# 1A_driver.net
KiCad netlist of a schematic drawn in EAGLE
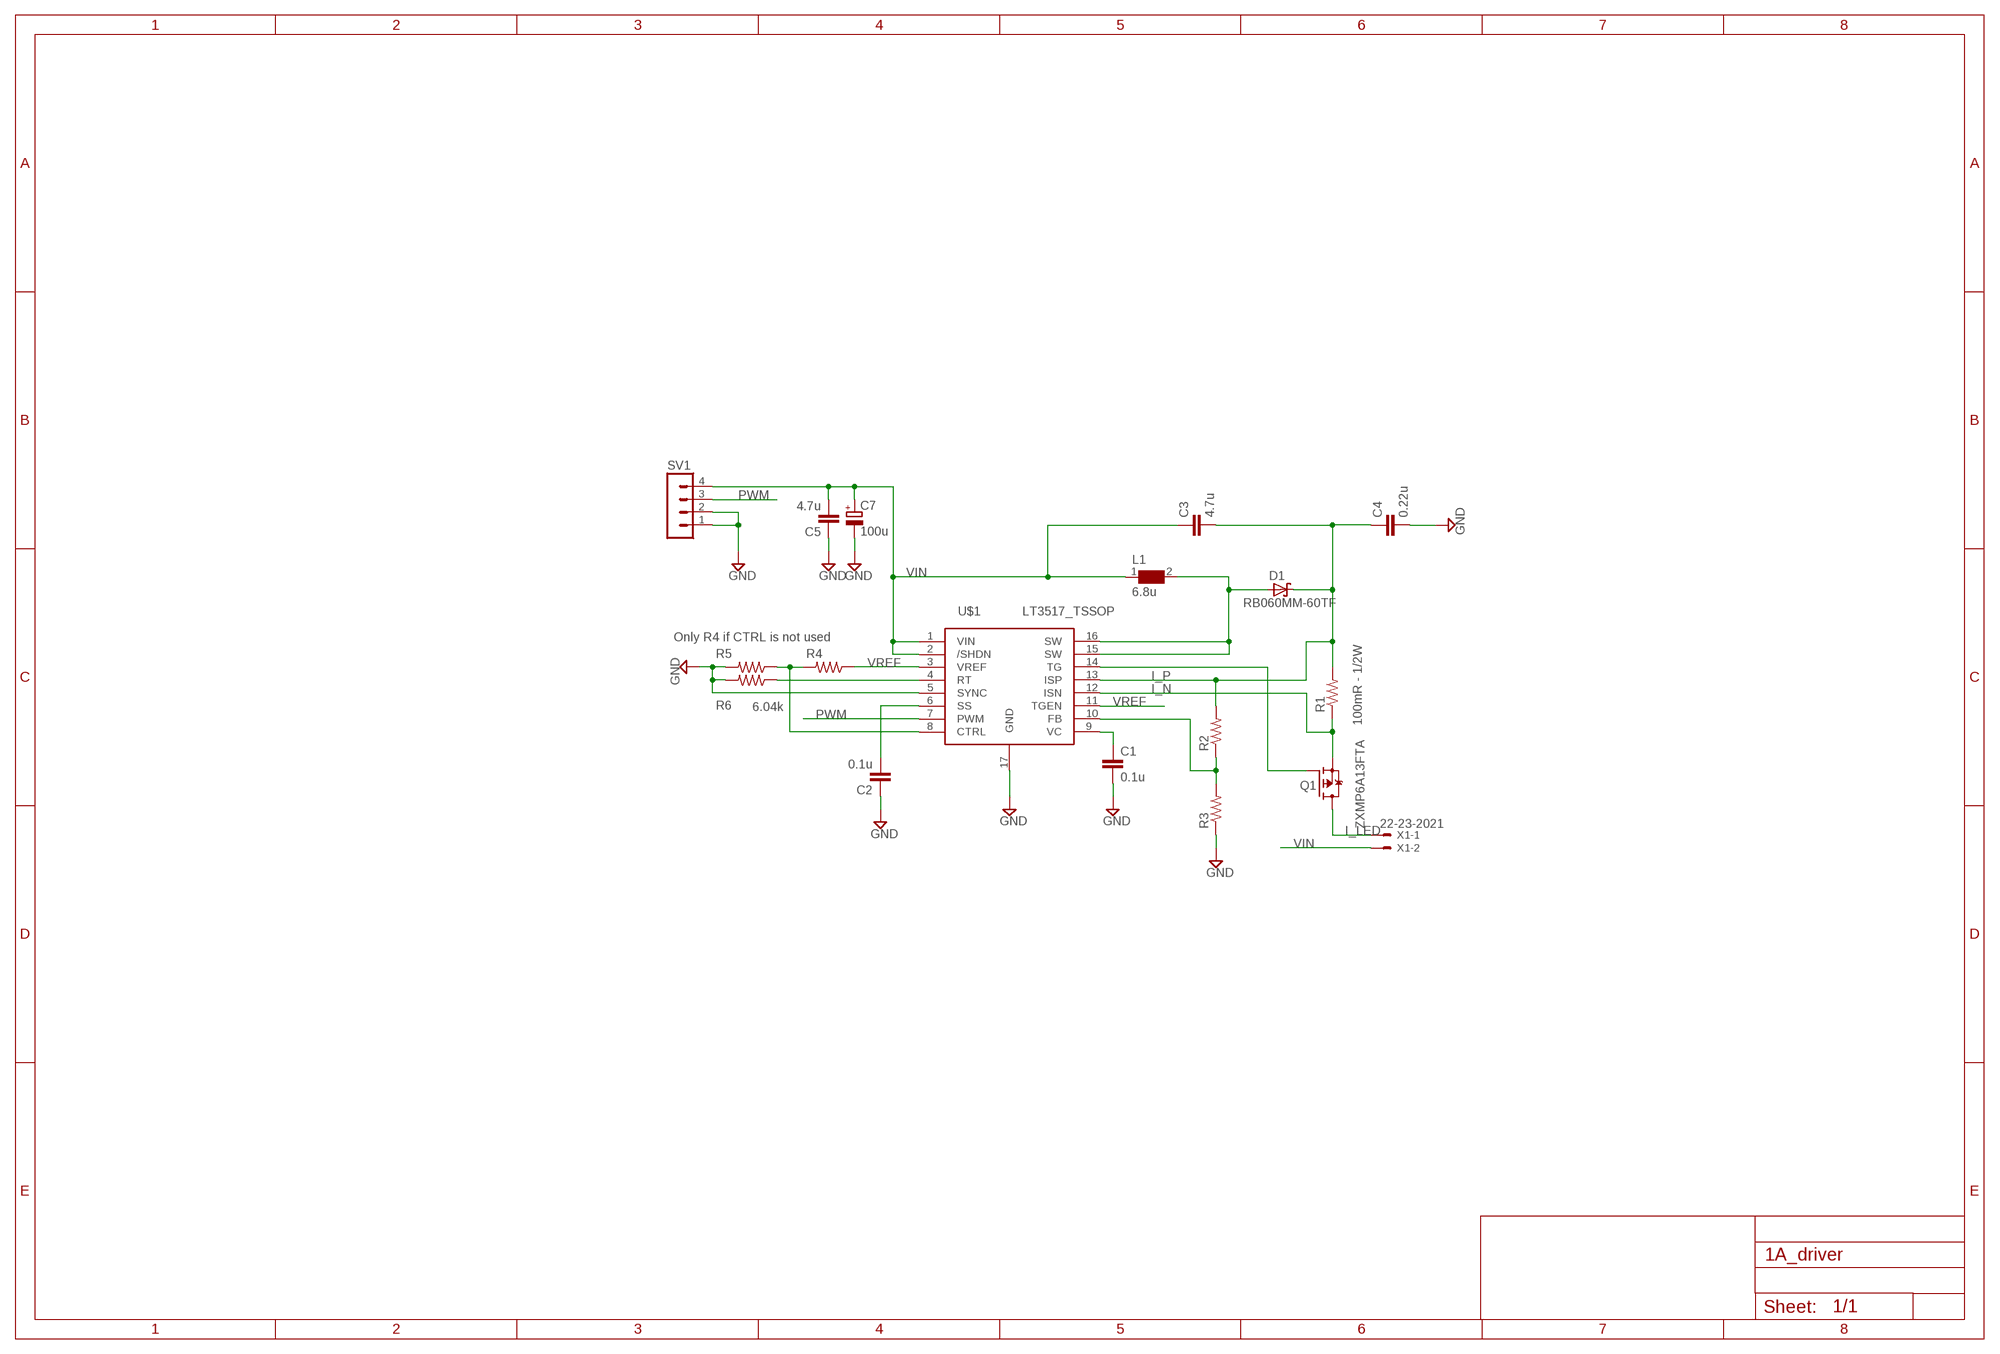
[diagram p0: schematic, sheet 1]

(export (version "E")
  (design (tool "Eeschema 10.0.6"))
  (components
    (comp (ref "C1")
      (value "0.1u")
      (footprint "eagle-import:R0603")
      (libsource (lib "eagle-import") (part "CAP_0603"))
    )
    (comp (ref "C2")
      (value "0.1u")
      (footprint "eagle-import:R0603")
      (libsource (lib "eagle-import") (part "CAP_0603"))
    )
    (comp (ref "C3")
      (value "4.7u")
      (footprint "eagle-import:R1206")
      (libsource (lib "eagle-import") (part "CAP_1206"))
    )
    (comp (ref "C4")
      (value "0.22u")
      (footprint "eagle-import:R0603")
      (libsource (lib "eagle-import") (part "CAP_0603"))
    )
    (comp (ref "C5")
      (value "4.7u")
      (footprint "eagle-import:R1206")
      (libsource (lib "eagle-import") (part "CAP_1206"))
    )
    (comp (ref "C7")
      (value "100u")
      (footprint "eagle-import:E5-5")
      (libsource (lib "eagle-import") (part "CPOL-EUE5-5"))
    )
    (comp (ref "D1")
      (value "RB060MM-60TF")
      (footprint "eagle-import:SOD123FL")
      (libsource (lib "eagle-import") (part "SCH_DIODE"))
    )
    (comp (ref "L1")
      (value "6.8u")
      (footprint "eagle-import:WE-PD_1260_1245_1280_1210")
      (fields (field (name "MPN") "744771006"))
      (libsource (lib "eagle-import") (part "WE-PD_1260/1245/1280/1210-744771006"))
    )
    (comp (ref "Q1")
      (value "ZXMP6A13FTA")
      (footprint "eagle-import:SOT23")
      (libsource (lib "eagle-import") (part "P-CHAN_MOSFET"))
    )
    (comp (ref "R1")
      (value "100mR - 1/2W")
      (footprint "eagle-import:R1206")
      (libsource (lib "eagle-import") (part "RES_1206"))
    )
    (comp (ref "R2")
      (value "RES_0603")
      (footprint "eagle-import:R0603")
      (libsource (lib "eagle-import") (part "RES_0603"))
    )
    (comp (ref "R3")
      (value "RES_0603")
      (footprint "eagle-import:R0603")
      (libsource (lib "eagle-import") (part "RES_0603"))
    )
    (comp (ref "R4")
      (value "RES_0603")
      (footprint "eagle-import:R0603")
      (libsource (lib "eagle-import") (part "RES_0603"))
    )
    (comp (ref "R5")
      (value "RES_0603")
      (footprint "eagle-import:R0603")
      (libsource (lib "eagle-import") (part "RES_0603"))
    )
    (comp (ref "R6")
      (value "6.04k")
      (footprint "eagle-import:R0603")
      (libsource (lib "eagle-import") (part "RES_0603"))
    )
    (comp (ref "SV1")
      (value "MA04-1")
      (footprint "eagle-import:MA04-1")
      (libsource (lib "eagle-import") (part "MA04-1"))
    )
    (comp (ref "U$1")
      (value "LT3517_TSSOP")
      (footprint "eagle-import:TSSOP16_PAD")
      (libsource (lib "eagle-import") (part "LT3517_TSSOP"))
    )
    (comp (ref "X1")
      (value "22-23-2021")
      (footprint "eagle-import:22-23-2021")
      (fields (field (name "MF") "MOLEX"))
      (libsource (lib "eagle-import") (part "22-23-2021"))
    )
  )
  (nets
    (net (code "1") (name "/I_LED") (class "Default")
      (node (ref "Q1") (pin "D") (pinfunction "D_D") (pintype "passive"))
      (node (ref "X1") (pin "1") (pinfunction "S_1") (pintype "passive"))
    )
    (net (code "2") (name "/I_N") (class "Default")
      (node (ref "Q1") (pin "S") (pinfunction "S_S") (pintype "passive"))
      (node (ref "R1") (pin "1") (pinfunction "1_1") (pintype "passive"))
      (node (ref "U$1") (pin "12") (pinfunction "ISN_12") (pintype "bidirectional"))
    )
    (net (code "3") (name "/I_P") (class "Default")
      (node (ref "C3") (pin "2") (pinfunction "2_2") (pintype "passive"))
      (node (ref "C4") (pin "1") (pinfunction "1_1") (pintype "passive"))
      (node (ref "D1") (pin "C") (pinfunction "C_C") (pintype "passive"))
      (node (ref "R1") (pin "2") (pinfunction "2_2") (pintype "passive"))
      (node (ref "R2") (pin "2") (pinfunction "2_2") (pintype "passive"))
      (node (ref "U$1") (pin "13") (pinfunction "ISP_13") (pintype "bidirectional"))
    )
    (net (code "4") (name "/PWM") (class "Default")
      (node (ref "SV1") (pin "3") (pinfunction "3_3") (pintype "passive"))
      (node (ref "U$1") (pin "7") (pinfunction "PWM_7") (pintype "bidirectional"))
    )
    (net (code "5") (name "/VIN") (class "Default")
      (node (ref "C3") (pin "1") (pinfunction "1_1") (pintype "passive"))
      (node (ref "C5") (pin "2") (pinfunction "2_2") (pintype "passive"))
      (node (ref "C7") (pin "+") (pinfunction "+_+") (pintype "passive"))
      (node (ref "L1") (pin "1") (pinfunction "1_1") (pintype "passive"))
      (node (ref "SV1") (pin "4") (pinfunction "4_4") (pintype "passive"))
      (node (ref "U$1") (pin "1") (pinfunction "VIN_1") (pintype "bidirectional"))
      (node (ref "U$1") (pin "2") (pinfunction "/SHDN_2") (pintype "bidirectional"))
      (node (ref "X1") (pin "2") (pinfunction "S_2") (pintype "passive"))
    )
    (net (code "6") (name "/VREF") (class "Default")
      (node (ref "R4") (pin "1") (pinfunction "1_1") (pintype "passive"))
      (node (ref "U$1") (pin "11") (pinfunction "TGEN_11") (pintype "bidirectional"))
      (node (ref "U$1") (pin "3") (pinfunction "VREF_3") (pintype "bidirectional"))
    )
    (net (code "7") (name "GND") (class "Default")
      (node (ref "C1") (pin "2") (pinfunction "2_2") (pintype "passive"))
      (node (ref "C2") (pin "1") (pinfunction "1_1") (pintype "passive"))
      (node (ref "C4") (pin "2") (pinfunction "2_2") (pintype "passive"))
      (node (ref "C5") (pin "1") (pinfunction "1_1") (pintype "passive"))
      (node (ref "C7") (pin "-") (pinfunction "-_-") (pintype "passive"))
      (node (ref "R3") (pin "1") (pinfunction "1_1") (pintype "passive"))
      (node (ref "R5") (pin "2") (pinfunction "2_2") (pintype "passive"))
      (node (ref "R6") (pin "2") (pinfunction "2_2") (pintype "passive"))
      (node (ref "SV1") (pin "1") (pinfunction "1_1") (pintype "passive"))
      (node (ref "SV1") (pin "2") (pinfunction "2_2") (pintype "passive"))
      (node (ref "U$1") (pin "17") (pinfunction "GND_17") (pintype "bidirectional"))
      (node (ref "U$1") (pin "5") (pinfunction "SYNC_5") (pintype "bidirectional"))
    )
    (net (code "8") (name "Net-(D1-PadA)") (class "Default")
      (node (ref "D1") (pin "A") (pinfunction "A_A") (pintype "passive"))
      (node (ref "L1") (pin "2") (pinfunction "2_2") (pintype "passive"))
      (node (ref "U$1") (pin "15") (pinfunction "SW_15") (pintype "bidirectional"))
      (node (ref "U$1") (pin "16") (pinfunction "SW_16") (pintype "bidirectional"))
    )
    (net (code "9") (name "Net-(U$1-CTRL)") (class "Default")
      (node (ref "R4") (pin "2") (pinfunction "2_2") (pintype "passive"))
      (node (ref "R5") (pin "1") (pinfunction "1_1") (pintype "passive"))
      (node (ref "U$1") (pin "8") (pinfunction "CTRL_8") (pintype "bidirectional"))
    )
    (net (code "10") (name "Net-(U$1-FB)") (class "Default")
      (node (ref "R2") (pin "1") (pinfunction "1_1") (pintype "passive"))
      (node (ref "R3") (pin "2") (pinfunction "2_2") (pintype "passive"))
      (node (ref "U$1") (pin "10") (pinfunction "FB_10") (pintype "bidirectional"))
    )
    (net (code "11") (name "Net-(U$1-RT)") (class "Default")
      (node (ref "R6") (pin "1") (pinfunction "1_1") (pintype "passive"))
      (node (ref "U$1") (pin "4") (pinfunction "RT_4") (pintype "bidirectional"))
    )
    (net (code "12") (name "Net-(U$1-SS)") (class "Default")
      (node (ref "C2") (pin "2") (pinfunction "2_2") (pintype "passive"))
      (node (ref "U$1") (pin "6") (pinfunction "SS_6") (pintype "bidirectional"))
    )
    (net (code "13") (name "Net-(U$1-TG)") (class "Default")
      (node (ref "Q1") (pin "G") (pinfunction "G_G") (pintype "passive"))
      (node (ref "U$1") (pin "14") (pinfunction "TG_14") (pintype "bidirectional"))
    )
    (net (code "14") (name "Net-(U$1-VC)") (class "Default")
      (node (ref "C1") (pin "1") (pinfunction "1_1") (pintype "passive"))
      (node (ref "U$1") (pin "9") (pinfunction "VC_9") (pintype "bidirectional"))
    )
  )
)
